# 18_IR_LED.net
KiCad netlist of a schematic drawn in Altium Designer
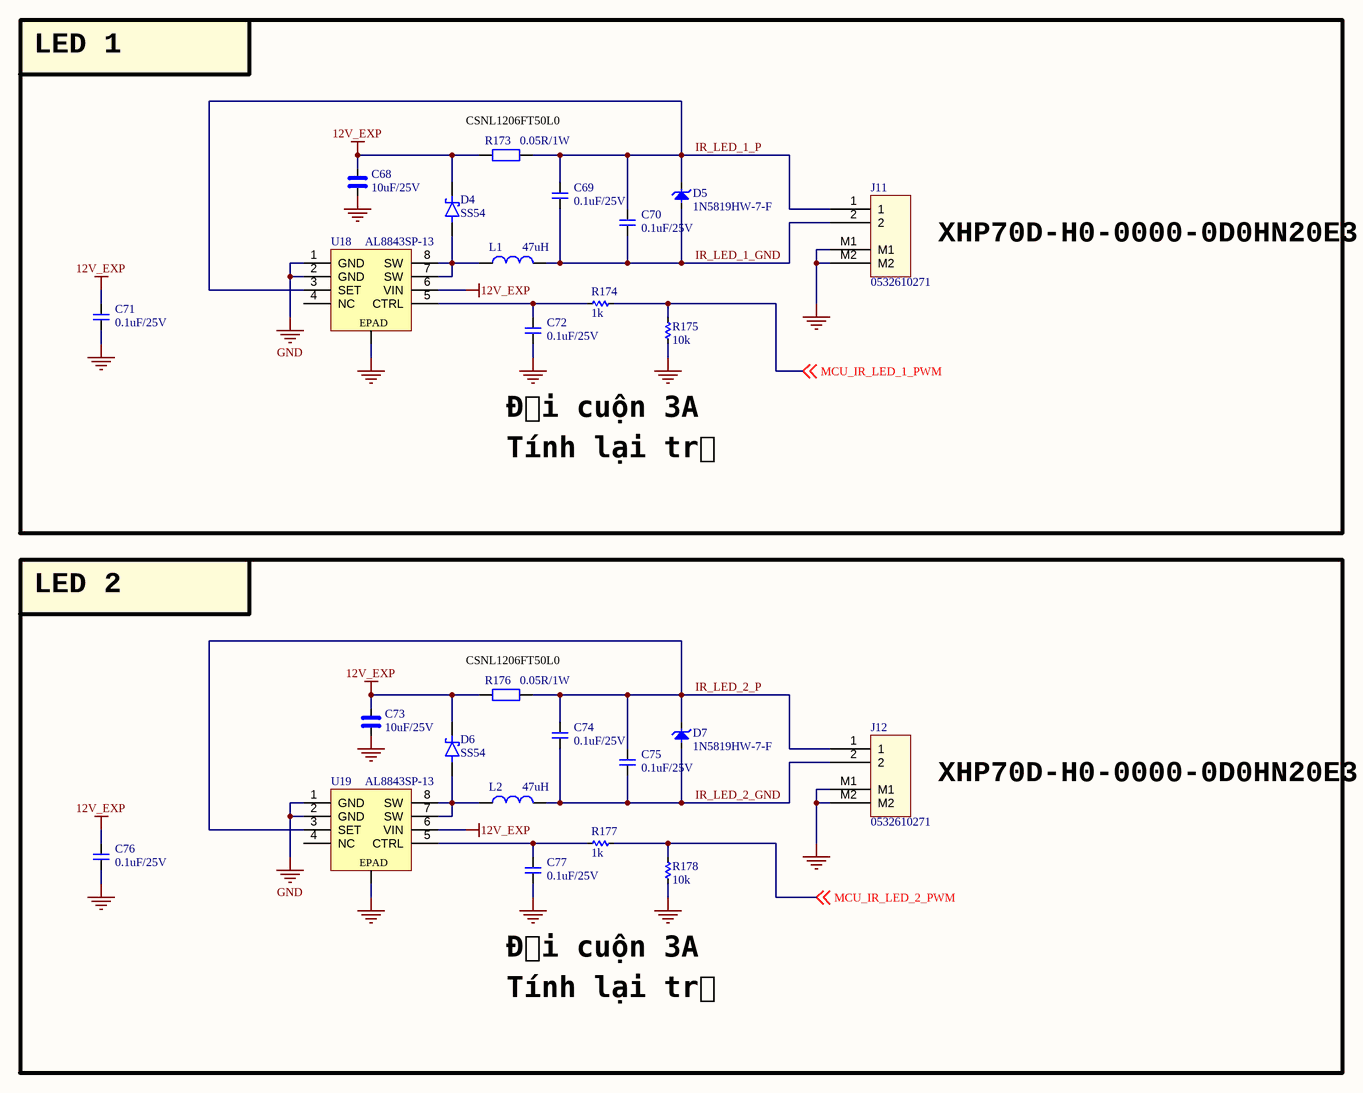
[diagram p0: 18_IR_LED.SchDoc]

(export (version "E")
  (design (tool "Eeschema 10.0.6"))
  (components
    (comp (ref "C68")
      (value "10uF/25V")
      (footprint "CAP_C_2012X110")
      (description "CAP High Value")
      (libsource (lib "LABLIB") (part "_CAP_C_High_2"))
    )
    (comp (ref "C69")
      (value "0.1uF/25V")
      (footprint "CAP_C_1608X80")
      (description "CAP")
      (libsource (lib "LABLIB") (part "_CAP_C_2"))
    )
    (comp (ref "C70")
      (value "0.1uF/25V")
      (footprint "CAP_C_1608X80")
      (description "CAP")
      (libsource (lib "LABLIB") (part "_CAP_C_2"))
    )
    (comp (ref "C71")
      (value "0.1uF/25V")
      (footprint "CAP_C_1608X80")
      (description "CAP")
      (libsource (lib "LABLIB") (part "_CAP_C_2"))
    )
    (comp (ref "C72")
      (value "0.1uF/25V")
      (footprint "CAP_C_1608X80")
      (description "CAP")
      (libsource (lib "LABLIB") (part "_CAP_C_2"))
    )
    (comp (ref "C73")
      (value "10uF/25V")
      (footprint "CAP_C_2012X110")
      (description "CAP High Value")
      (libsource (lib "LABLIB") (part "_CAP_C_High_2"))
    )
    (comp (ref "C74")
      (value "0.1uF/25V")
      (footprint "CAP_C_1608X80")
      (description "CAP")
      (libsource (lib "LABLIB") (part "_CAP_C_2"))
    )
    (comp (ref "C75")
      (value "0.1uF/25V")
      (footprint "CAP_C_1608X80")
      (description "CAP")
      (libsource (lib "LABLIB") (part "_CAP_C_2"))
    )
    (comp (ref "C76")
      (value "0.1uF/25V")
      (footprint "CAP_C_1608X80")
      (description "CAP")
      (libsource (lib "LABLIB") (part "_CAP_C_2"))
    )
    (comp (ref "C77")
      (value "0.1uF/25V")
      (footprint "CAP_C_1608X80")
      (description "CAP")
      (libsource (lib "LABLIB") (part "_CAP_C_2"))
    )
    (comp (ref "D4")
      (value "SS54")
      (footprint "DO-214AC_SMA")
      (description "DIODE SCHOTTKY")
      (libsource (lib "LABLIB") (part "DIODE SCHOTTKY"))
    )
    (comp (ref "D5")
      (value "1N5819HW-7-F")
      (footprint "SOD3717X145N")
      (description "Zenner")
      (libsource (lib "LABLIB") (part "DIODE Zener"))
    )
    (comp (ref "D6")
      (value "SS54")
      (footprint "DO-214AC_SMA")
      (description "DIODE SCHOTTKY")
      (libsource (lib "LABLIB") (part "DIODE SCHOTTKY"))
    )
    (comp (ref "D7")
      (value "1N5819HW-7-F")
      (footprint "SOD3717X145N")
      (description "Zenner")
      (libsource (lib "LABLIB") (part "DIODE Zener"))
    )
    (comp (ref "J11")
      (value "0532610271")
      (footprint "MOLEX_0532610271")
      (libsource (lib "LABLIB") (part "Header 2x1_2M"))
    )
    (comp (ref "J12")
      (value "0532610271")
      (footprint "MOLEX_0532610271")
      (libsource (lib "LABLIB") (part "Header 2x1_2M"))
    )
    (comp (ref "L1")
      (value "47uH")
      (footprint "IND_MP_1250x1250x850")
      (description "B82477P4473M000")
      (fields
        (field (name "PARTNO") "78477010")
        (field (name "MANUFACTURER") "Wurth Elektronik")
        (field (name "CREATED BY") "Baojun Chen")
      )
      (libsource (lib "BEE-DAL_EXP_sche") (part "L-SMD-1"))
    )
    (comp (ref "L2")
      (value "47uH")
      (footprint "IND_MP_1250x1250x850")
      (description "B82477P4473M000")
      (fields
        (field (name "PARTNO") "78477010")
        (field (name "MANUFACTURER") "Wurth Elektronik")
        (field (name "CREATED BY") "Baojun Chen")
      )
      (libsource (lib "BEE-DAL_EXP_sche") (part "L-SMD-1"))
    )
    (comp (ref "R173")
      (value "0.05R/1W")
      (footprint "RES_C_3216X70")
      (description "RES")
      (libsource (lib "LABLIB") (part "_RES"))
    )
    (comp (ref "R174")
      (value "1k")
      (footprint "RES_C_1608X60")
      (description "RES")
      (libsource (lib "LABLIB") (part "_RES_B_2"))
    )
    (comp (ref "R175")
      (value "10k")
      (footprint "RES_C_1608X60")
      (description "RES")
      (libsource (lib "LABLIB") (part "_RES_B_2"))
    )
    (comp (ref "R176")
      (value "0.05R/1W")
      (footprint "RES_C_3216X70")
      (description "RES")
      (libsource (lib "LABLIB") (part "_RES"))
    )
    (comp (ref "R177")
      (value "1k")
      (footprint "RES_C_1608X60")
      (description "RES")
      (libsource (lib "LABLIB") (part "_RES_B_2"))
    )
    (comp (ref "R178")
      (value "10k")
      (footprint "RES_C_1608X60")
      (description "RES")
      (libsource (lib "LABLIB") (part "_RES_B_2"))
    )
    (comp (ref "U18")
      (value "AL8843SP-13")
      (footprint "SOIC127P602X173-8N_EPAD")
      (description "IC LED DRIVER RGLTR PWM 3A 8SO")
      (libsource (lib "BEE-DAL_EXP_sche") (part "AL8843SP-13"))
    )
    (comp (ref "U19")
      (value "AL8843SP-13")
      (footprint "SOIC127P602X173-8N_EPAD")
      (description "IC LED DRIVER RGLTR PWM 3A 8SO")
      (libsource (lib "BEE-DAL_EXP_sche") (part "AL8843SP-13"))
    )
  )
  (nets
    (net (code "1") (name "/IR_LED_1_GND") (class "Default")
      (node (ref "C69") (pin "1") (pinfunction "1_1") (pintype "passive"))
      (node (ref "C70") (pin "1") (pinfunction "1_1") (pintype "passive"))
      (node (ref "D5") (pin "2") (pinfunction "A_2") (pintype "passive"))
      (node (ref "J11") (pin "2") (pinfunction "2_2") (pintype "passive"))
      (node (ref "L1") (pin "2") (pinfunction "2_2") (pintype "passive"))
    )
    (net (code "2") (name "/IR_LED_1_P") (class "Default")
      (node (ref "C69") (pin "2") (pinfunction "2_2") (pintype "passive"))
      (node (ref "C70") (pin "2") (pinfunction "2_2") (pintype "passive"))
      (node (ref "D5") (pin "1") (pinfunction "K_1") (pintype "passive"))
      (node (ref "J11") (pin "1") (pinfunction "1_1") (pintype "passive"))
      (node (ref "R173") (pin "2") (pinfunction "2_2") (pintype "passive"))
      (node (ref "U18") (pin "3") (pinfunction "SET_3") (pintype "passive"))
    )
    (net (code "3") (name "/IR_LED_2_GND") (class "Default")
      (node (ref "C74") (pin "1") (pinfunction "1_1") (pintype "passive"))
      (node (ref "C75") (pin "1") (pinfunction "1_1") (pintype "passive"))
      (node (ref "D7") (pin "2") (pinfunction "A_2") (pintype "passive"))
      (node (ref "J12") (pin "2") (pinfunction "2_2") (pintype "passive"))
      (node (ref "L2") (pin "2") (pinfunction "2_2") (pintype "passive"))
    )
    (net (code "4") (name "/IR_LED_2_P") (class "Default")
      (node (ref "C74") (pin "2") (pinfunction "2_2") (pintype "passive"))
      (node (ref "C75") (pin "2") (pinfunction "2_2") (pintype "passive"))
      (node (ref "D7") (pin "1") (pinfunction "K_1") (pintype "passive"))
      (node (ref "J12") (pin "1") (pinfunction "1_1") (pintype "passive"))
      (node (ref "R176") (pin "2") (pinfunction "2_2") (pintype "passive"))
      (node (ref "U19") (pin "3") (pinfunction "SET_3") (pintype "passive"))
    )
    (net (code "5") (name "12V_EXP") (class "Default")
      (node (ref "C68") (pin "1") (pinfunction "1_1") (pintype "passive"))
      (node (ref "C71") (pin "2") (pinfunction "2_2") (pintype "passive"))
      (node (ref "C73") (pin "1") (pinfunction "1_1") (pintype "passive"))
      (node (ref "C76") (pin "2") (pinfunction "2_2") (pintype "passive"))
      (node (ref "D4") (pin "1") (pinfunction "K_1") (pintype "passive"))
      (node (ref "D6") (pin "1") (pinfunction "K_1") (pintype "passive"))
      (node (ref "R173") (pin "1") (pinfunction "1_1") (pintype "passive"))
      (node (ref "R176") (pin "1") (pinfunction "1_1") (pintype "passive"))
      (node (ref "U18") (pin "6") (pinfunction "VIN_6") (pintype "passive"))
      (node (ref "U19") (pin "6") (pinfunction "VIN_6") (pintype "passive"))
    )
    (net (code "6") (name "GND") (class "Default")
      (node (ref "C68") (pin "2") (pinfunction "2_2") (pintype "passive"))
      (node (ref "C71") (pin "1") (pinfunction "1_1") (pintype "passive"))
      (node (ref "C72") (pin "1") (pinfunction "1_1") (pintype "passive"))
      (node (ref "C73") (pin "2") (pinfunction "2_2") (pintype "passive"))
      (node (ref "C76") (pin "1") (pinfunction "1_1") (pintype "passive"))
      (node (ref "C77") (pin "1") (pinfunction "1_1") (pintype "passive"))
      (node (ref "J11") (pin "M1") (pinfunction "M1_M1") (pintype "passive"))
      (node (ref "J11") (pin "M2") (pinfunction "M2_M2") (pintype "passive"))
      (node (ref "J12") (pin "M1") (pinfunction "M1_M1") (pintype "passive"))
      (node (ref "J12") (pin "M2") (pinfunction "M2_M2") (pintype "passive"))
      (node (ref "R175") (pin "2") (pinfunction "2_2") (pintype "passive"))
      (node (ref "R178") (pin "2") (pinfunction "2_2") (pintype "passive"))
      (node (ref "U18") (pin "1") (pinfunction "GND_1") (pintype "passive"))
      (node (ref "U18") (pin "2") (pinfunction "GND_2") (pintype "passive"))
      (node (ref "U18") (pin "9") (pinfunction "EPAD_9") (pintype "passive"))
      (node (ref "U19") (pin "1") (pinfunction "GND_1") (pintype "passive"))
      (node (ref "U19") (pin "2") (pinfunction "GND_2") (pintype "passive"))
      (node (ref "U19") (pin "9") (pinfunction "EPAD_9") (pintype "passive"))
    )
    (net (code "7") (name "MCU_IR_LED_1_PWM") (class "Default")
      (node (ref "R174") (pin "2") (pinfunction "2_2") (pintype "passive"))
      (node (ref "R175") (pin "1") (pinfunction "1_1") (pintype "passive"))
    )
    (net (code "8") (name "MCU_IR_LED_2_PWM") (class "Default")
      (node (ref "R177") (pin "2") (pinfunction "2_2") (pintype "passive"))
      (node (ref "R178") (pin "1") (pinfunction "1_1") (pintype "passive"))
    )
    (net (code "9") (name "Net-(D4-A)") (class "Default")
      (node (ref "D4") (pin "2") (pinfunction "A_2") (pintype "passive"))
      (node (ref "L1") (pin "1") (pinfunction "1_1") (pintype "passive"))
      (node (ref "U18") (pin "7") (pinfunction "SW_7") (pintype "passive"))
      (node (ref "U18") (pin "8") (pinfunction "SW_8") (pintype "passive"))
    )
    (net (code "10") (name "Net-(D6-A)") (class "Default")
      (node (ref "D6") (pin "2") (pinfunction "A_2") (pintype "passive"))
      (node (ref "L2") (pin "1") (pinfunction "1_1") (pintype "passive"))
      (node (ref "U19") (pin "7") (pinfunction "SW_7") (pintype "passive"))
      (node (ref "U19") (pin "8") (pinfunction "SW_8") (pintype "passive"))
    )
    (net (code "11") (name "Net-(U18-CTRL)") (class "Default")
      (node (ref "C72") (pin "2") (pinfunction "2_2") (pintype "passive"))
      (node (ref "R174") (pin "1") (pinfunction "1_1") (pintype "passive"))
      (node (ref "U18") (pin "5") (pinfunction "CTRL_5") (pintype "passive"))
    )
    (net (code "12") (name "Net-(U19-CTRL)") (class "Default")
      (node (ref "C77") (pin "2") (pinfunction "2_2") (pintype "passive"))
      (node (ref "R177") (pin "1") (pinfunction "1_1") (pintype "passive"))
      (node (ref "U19") (pin "5") (pinfunction "CTRL_5") (pintype "passive"))
    )
    (net (code "13") (name "unconnected-(U18-NC-Pad4)") (class "Default")
      (node (ref "U18") (pin "4") (pinfunction "NC_4") (pintype "passive"))
    )
    (net (code "14") (name "unconnected-(U19-NC-Pad4)") (class "Default")
      (node (ref "U19") (pin "4") (pinfunction "NC_4") (pintype "passive"))
    )
  )
)
